# AD8428.net
KiCad netlist of a schematic drawn in EAGLE
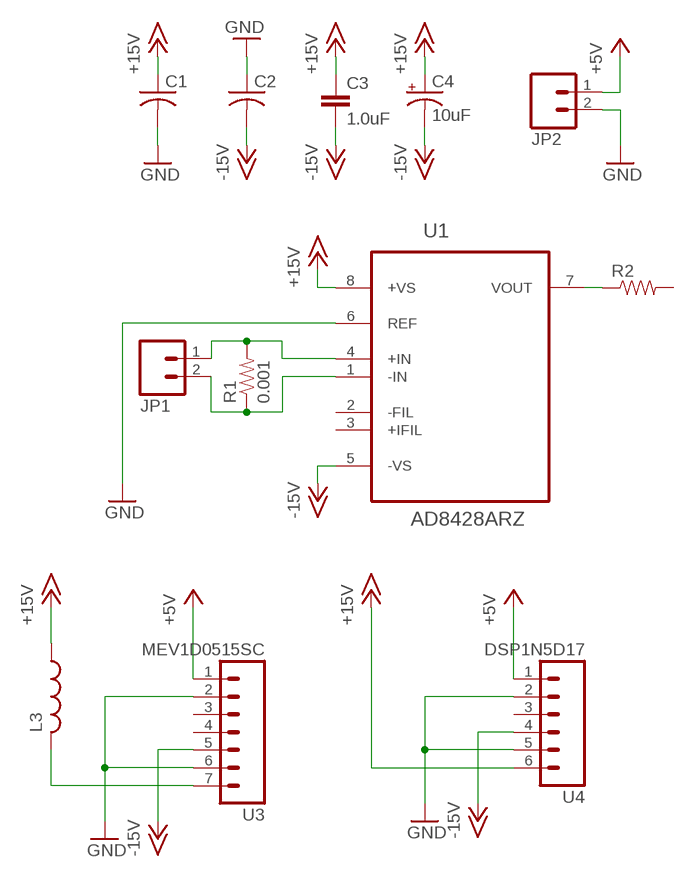
[diagram p0: schematic, sheet 1]

(export (version "E")
  (design (tool "Eeschema 10.0.6"))
  (components
    (comp (ref "C1")
      (value "C-USC0603")
      (footprint "eagle-import:C0603")
      (libsource (lib "eagle-import") (part "C-USC0603"))
    )
    (comp (ref "C2")
      (value "C-USC0603")
      (footprint "eagle-import:C0603")
      (libsource (lib "eagle-import") (part "C-USC0603"))
    )
    (comp (ref "C3")
      (value "1.0uF")
      (footprint "eagle-import:1206")
      (libsource (lib "eagle-import") (part "1.0UF50V10%(1206)"))
    )
    (comp (ref "C4")
      (value "10uF")
      (footprint "eagle-import:EIA3216")
      (libsource (lib "eagle-import") (part "CAP_POL1206"))
    )
    (comp (ref "JP1")
      (value "M025MM")
      (footprint "eagle-import:SCREWTERMINAL-5MM-2")
      (libsource (lib "eagle-import") (part "M025MM"))
    )
    (comp (ref "JP2")
      (value "M025MM")
      (footprint "eagle-import:SCREWTERMINAL-5MM-2")
      (libsource (lib "eagle-import") (part "M025MM"))
    )
    (comp (ref "L3")
      (value "L-USL2825P")
      (footprint "eagle-import:L2825P")
      (libsource (lib "eagle-import") (part "L-USL2825P"))
    )
    (comp (ref "R1")
      (value "0.001")
      (footprint "eagle-import:2512")
      (libsource (lib "eagle-import") (part "0.001OHM-3W-1%(2512)3W/1%"))
    )
    (comp (ref "R2")
      (value "RESISTOR0805-RES")
      (footprint "eagle-import:0805")
      (libsource (lib "eagle-import") (part "RESISTOR0805-RES"))
    )
    (comp (ref "U1")
      (value "AD8428ARZ")
      (footprint "eagle-import:SOIC127P600X175-8N")
      (libsource (lib "eagle-import") (part "AD8428ARZ"))
    )
    (comp (ref "U3")
      (value "MEV1D0515SC")
      (footprint "eagle-import:1X07")
      (libsource (lib "eagle-import") (part "M07"))
    )
    (comp (ref "U4")
      (value "DSP1N5D17")
      (footprint "eagle-import:1X06")
      (libsource (lib "eagle-import") (part "M06SILK_FEMALE_PTH"))
    )
  )
  (nets
    (net (code "1") (name "+5V") (class "Default")
      (node (ref "JP2") (pin "1") (pinfunction "1_1") (pintype "passive"))
      (node (ref "U3") (pin "1") (pinfunction "1_1") (pintype "passive"))
      (node (ref "U4") (pin "1") (pinfunction "1_1") (pintype "passive"))
    )
    (net (code "2") (name "+15V") (class "Default")
      (node (ref "C1") (pin "1") (pinfunction "1_1") (pintype "passive"))
      (node (ref "C3") (pin "1") (pinfunction "1_1") (pintype "passive"))
      (node (ref "C4") (pin "A") (pinfunction "+_A") (pintype "passive"))
      (node (ref "L3") (pin "1") (pinfunction "1_1") (pintype "passive"))
      (node (ref "U1") (pin "8") (pinfunction "+VS_8") (pintype "power_in"))
      (node (ref "U4") (pin "6") (pinfunction "6_6") (pintype "passive"))
    )
    (net (code "3") (name "-15V") (class "Default")
      (node (ref "C2") (pin "2") (pinfunction "2_2") (pintype "passive"))
      (node (ref "C3") (pin "2") (pinfunction "2_2") (pintype "passive"))
      (node (ref "C4") (pin "C") (pinfunction "-_C") (pintype "passive"))
      (node (ref "U1") (pin "5") (pinfunction "-VS_5") (pintype "power_in"))
      (node (ref "U3") (pin "5") (pinfunction "5_5") (pintype "passive"))
      (node (ref "U4") (pin "4") (pinfunction "4_4") (pintype "passive"))
    )
    (net (code "4") (name "GND") (class "Default")
      (node (ref "C1") (pin "2") (pinfunction "2_2") (pintype "passive"))
      (node (ref "C2") (pin "1") (pinfunction "1_1") (pintype "passive"))
      (node (ref "JP2") (pin "2") (pinfunction "2_2") (pintype "passive"))
      (node (ref "U1") (pin "6") (pinfunction "REF_6") (pintype "passive"))
      (node (ref "U3") (pin "2") (pinfunction "2_2") (pintype "passive"))
      (node (ref "U3") (pin "6") (pinfunction "6_6") (pintype "passive"))
      (node (ref "U4") (pin "2") (pinfunction "2_2") (pintype "passive"))
      (node (ref "U4") (pin "5") (pinfunction "5_5") (pintype "passive"))
    )
    (net (code "5") (name "Net-(L3-Pad2)") (class "Default")
      (node (ref "L3") (pin "2") (pinfunction "2_2") (pintype "passive"))
      (node (ref "U3") (pin "7") (pinfunction "7_7") (pintype "passive"))
    )
    (net (code "6") (name "Net-(U1-+IN)") (class "Default")
      (node (ref "JP1") (pin "1") (pinfunction "1_1") (pintype "passive"))
      (node (ref "R1") (pin "2") (pinfunction "2_2") (pintype "passive"))
      (node (ref "U1") (pin "4") (pinfunction "+IN_4") (pintype "input"))
    )
    (net (code "7") (name "Net-(U1--IN)") (class "Default")
      (node (ref "JP1") (pin "2") (pinfunction "2_2") (pintype "passive"))
      (node (ref "R1") (pin "1") (pinfunction "1_1") (pintype "passive"))
      (node (ref "U1") (pin "1") (pinfunction "-IN_1") (pintype "input"))
    )
    (net (code "8") (name "Net-(U1-VOUT)") (class "Default")
      (node (ref "R2") (pin "1") (pinfunction "1_1") (pintype "passive"))
      (node (ref "U1") (pin "7") (pinfunction "VOUT_7") (pintype "output"))
    )
    (net (code "9") (name "unconnected-(R2-Pad2)") (class "Default")
      (node (ref "R2") (pin "2") (pinfunction "2_2") (pintype "passive"))
    )
    (net (code "10") (name "unconnected-(U1-+IFIL-Pad3)") (class "Default")
      (node (ref "U1") (pin "3") (pinfunction "+IFIL_3") (pintype "input"))
    )
    (net (code "11") (name "unconnected-(U1--FIL-Pad2)") (class "Default")
      (node (ref "U1") (pin "2") (pinfunction "-FIL_2") (pintype "input"))
    )
    (net (code "12") (name "unconnected-(U3-Pad3)") (class "Default")
      (node (ref "U3") (pin "3") (pinfunction "3_3") (pintype "passive"))
    )
    (net (code "13") (name "unconnected-(U3-Pad4)") (class "Default")
      (node (ref "U3") (pin "4") (pinfunction "4_4") (pintype "passive"))
    )
    (net (code "14") (name "unconnected-(U4-Pad3)") (class "Default")
      (node (ref "U4") (pin "3") (pinfunction "3_3") (pintype "passive"))
    )
  )
)
